# ole_minifat.net
KiCad netlist of a schematic drawn in Altium Designer
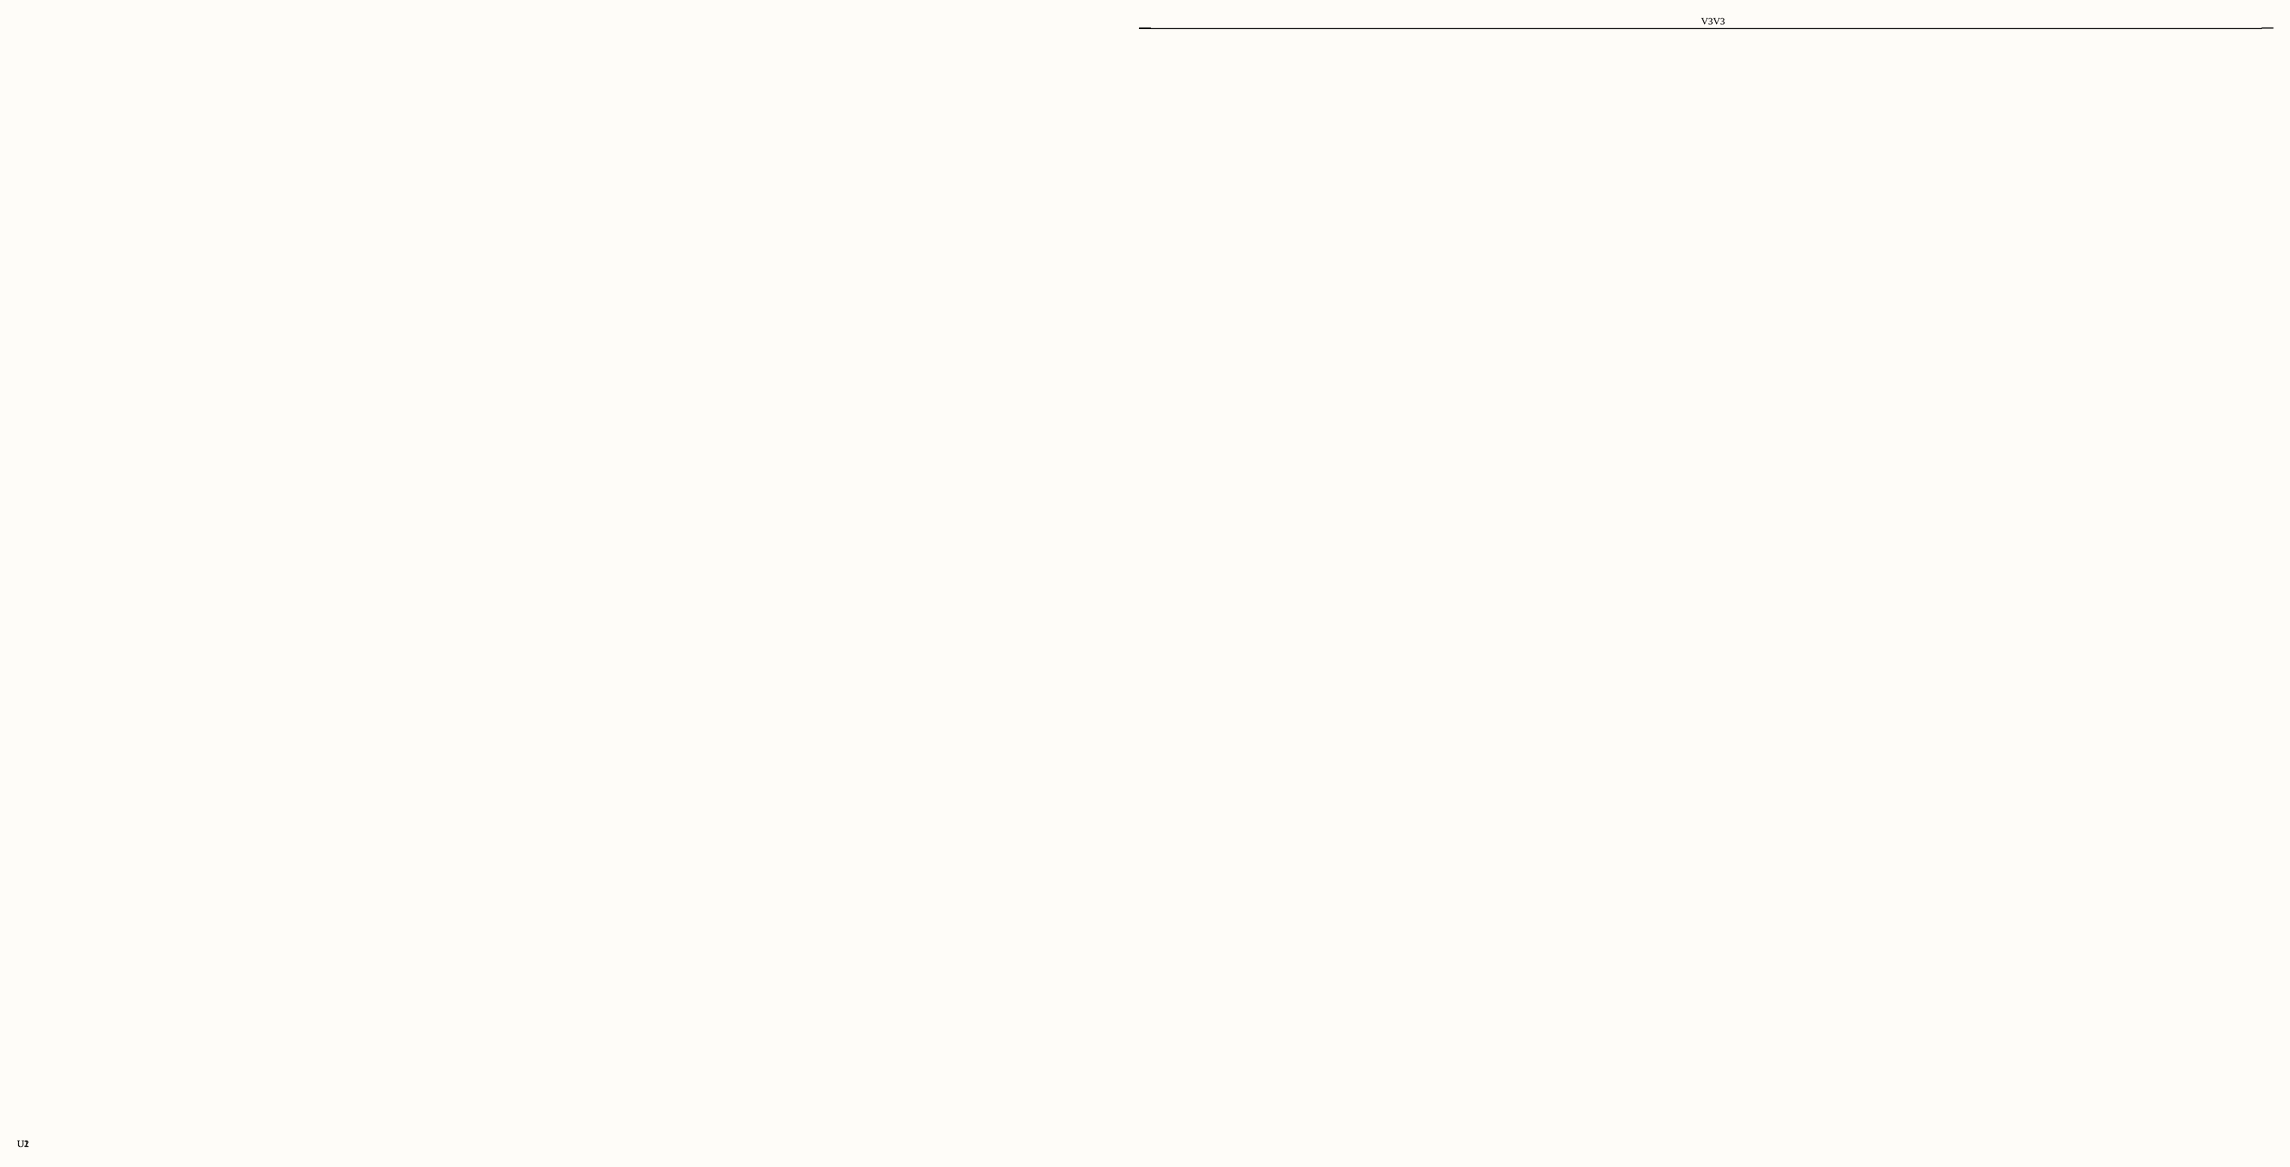
[diagram p0: ole_minifat.SchDoc]

(export (version "E")
  (design (tool "Eeschema 10.0.6"))
  (components
    (comp (ref "U1") (value "~") (libsource (lib "altium-import") (part "root_0_RES_")))
    (comp (ref "U2") (value "~") (libsource (lib "altium-import") (part "root_0_CAP_")))
  )
  (nets
    (net (code "1") (name "/V3V3") (class "Default")
      (node (ref "U1") (pin "1") (pinfunction "P0.25_1") (pintype "passive"))
      (node (ref "U2") (pin "1") (pinfunction "VDD_1") (pintype "power_in"))
    )
  )
)
